# isoDebug-Connectors.net
KiCad netlist of a schematic drawn in Altium Designer
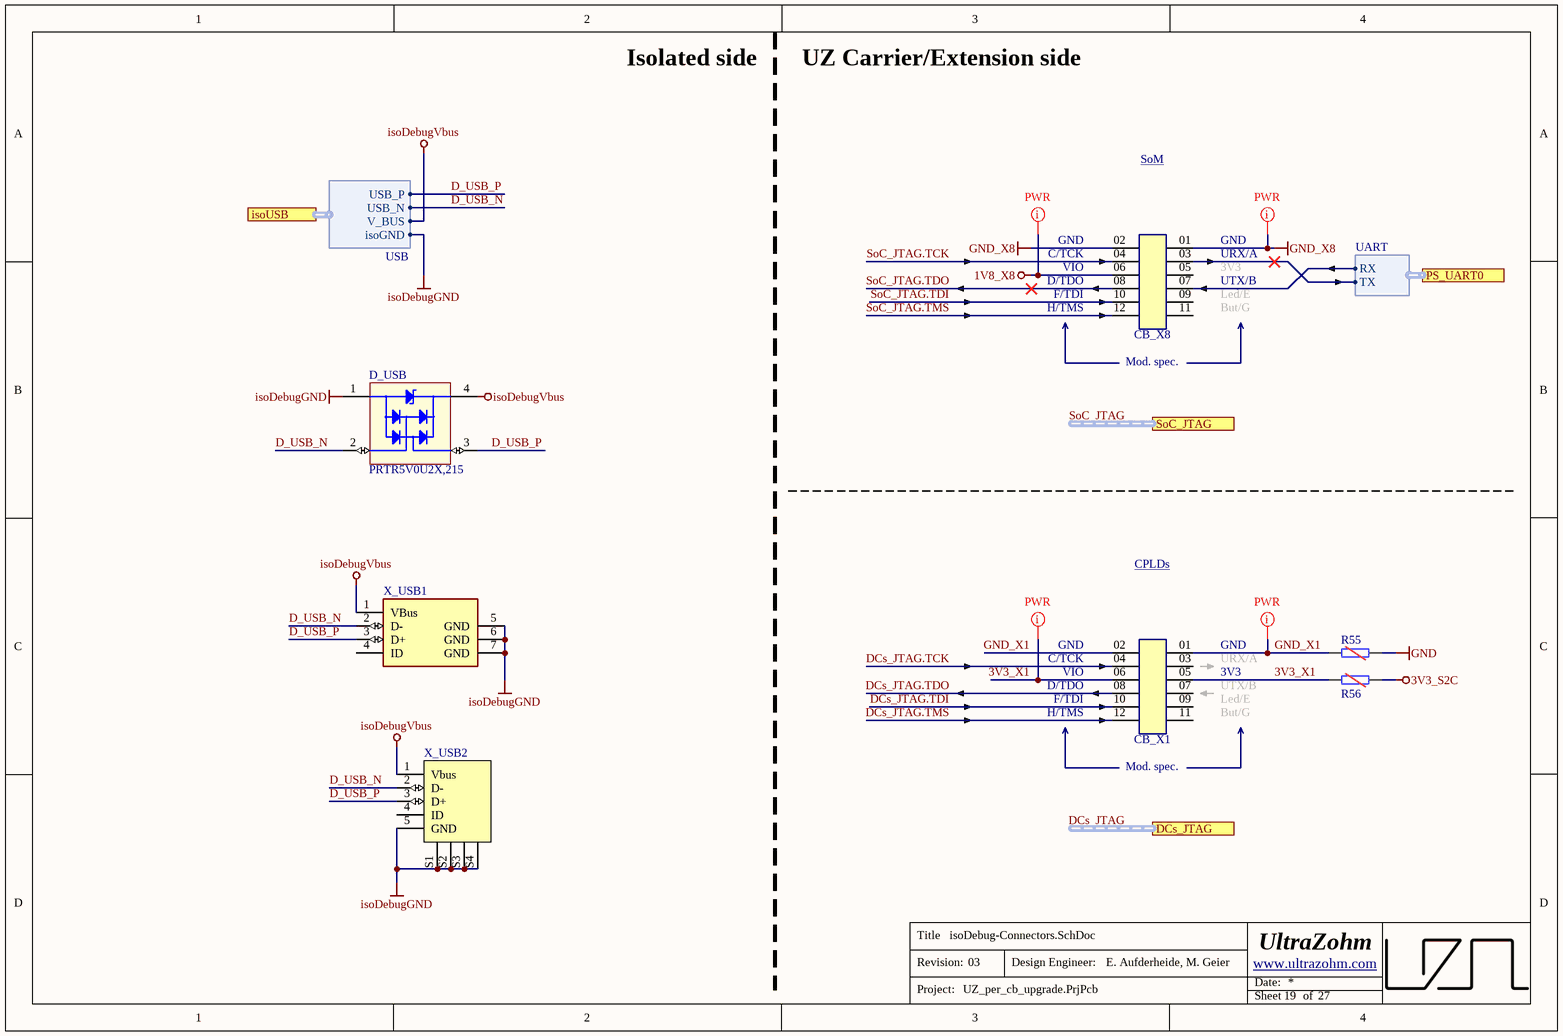
[diagram p0: isoDebug-Connectors.SchDoc]

(export (version "E")
  (design (tool "Eeschema 10.0.6"))
  (components
    (comp (ref "CB_X1")
      (value "PH 0.1\" SMD 2x06")
      (footprint "TSM-106-01-L-DV_Mirrored12+Triangle02")
      (fields
        (field (name "MANUFACTURER PART NUMBER") "UZgen_Conn_PinHead_2x06_SMD_100mil_90deg_mirrored12triangle02")
        (field (name "MANUFACTURER") "UZgen")
        (field (name "CREATED FROM") "UZgenTool")
      )
      (libsource (lib "user") (part "PinHeader_2x06_Mirrored12"))
    )
    (comp (ref "CB_X8")
      (value "PH 0.1\" SMD 2x06")
      (footprint "TSM-106-01-L-DV_Mirrored12+Triangle02")
      (fields
        (field (name "MANUFACTURER PART NUMBER") "UZgen_Conn_PinHead_2x06_SMD_100mil_90deg_mirrored12triangle02")
        (field (name "MANUFACTURER") "UZgen")
        (field (name "CREATED FROM") "UZgenTool")
      )
      (libsource (lib "user") (part "PinHeader_2x06_Mirrored12"))
    )
    (comp (ref "D_USB")
      (value "PRTR5V0U2X,215")
      (footprint "SOT-143B-4")
      (description "ESD Suppressors / TVS Diodes PRTR5V0U2X/SOT143/SOT4")
      (fields
        (field (name "MANUFACTURER") "Nexperia")
        (field (name "LCSC PART NUMBER") "C12333")
        (field (name "CREATED FROM") "AGeiger")
      )
      (libsource (lib "user") (part "CD143A-SRxx"))
    )
    (comp (ref "R55")
      (value "DNP")
      (footprint "R_1206_TE-DNP")
      (description "Generic resistor (DNP)")
      (fields
        (field (name "MANUFACTURER PART NUMBER") "UZgen_R_1206_DNP")
        (field (name "MANUFACTURER") "UZgen")
        (field (name "CREATED FROM") "UZgenTool")
      )
      (libsource (lib "user") (part "RES-DNP"))
    )
    (comp (ref "R56")
      (value "DNP")
      (footprint "R_1206_TE-DNP")
      (description "Generic resistor (DNP)")
      (fields
        (field (name "MANUFACTURER PART NUMBER") "UZgen_R_1206_DNP")
        (field (name "MANUFACTURER") "UZgen")
        (field (name "CREATED FROM") "UZgenTool")
      )
      (libsource (lib "user") (part "RES-DNP"))
    )
    (comp (ref "X_USB1")
      (value "Mini USB 90")
      (footprint "920-462A2021Y10102_CUSTOMANLRING0.2mm")
      (description "USB 2.0 1 5P Female Mini-B Plugin USB Connectors ROHS")
      (fields
        (field (name "MANUFACTURER PART NUMBER") "920-462A2021Y10102")
        (field (name "MANUFACTURER") "Jing Extension of the Electronic Co.")
        (field (name "CREATED FROM") "FRosner")
      )
      (libsource (lib "user") (part "Mini_USB_90"))
    )
    (comp (ref "X_USB2")
      (value "Mini USB")
      (footprint "MINI_USB_5S_B _TYPE")
      (description "1A 1 Surface Mount 5P Female -30℃~+80℃ SMD USB Connectors ROHS")
      (fields
        (field (name "MANUFACTURER PART NUMBER") "MINI 5PTP")
        (field (name "MANUFACTURER") "SHOU HAN")
        (field (name "CREATED FROM") "AGeiger")
      )
      (libsource (lib "user") (part "Mini_USB"))
    )
  )
  (nets
    (net (code "5") (name "/3V3_X1") (class "Default")
      (node (ref "CB_X1") (pin "05") (pinfunction "05_05") (pintype "passive"))
      (node (ref "CB_X1") (pin "06") (pinfunction "06_06") (pintype "passive"))
      (node (ref "R56") (pin "1") (pinfunction "1_1") (pintype "passive"))
    )
    (net (code "6") (name "/DCs_JTAG.TCK") (class "Default")
      (node (ref "CB_X1") (pin "04") (pinfunction "04_04") (pintype "passive"))
    )
    (net (code "7") (name "/DCs_JTAG.TDI") (class "Default")
      (node (ref "CB_X1") (pin "10") (pinfunction "10_10") (pintype "passive"))
    )
    (net (code "8") (name "/DCs_JTAG.TDO") (class "Default")
      (node (ref "CB_X1") (pin "08") (pinfunction "08_08") (pintype "passive"))
    )
    (net (code "9") (name "/DCs_JTAG.TMS") (class "Default")
      (node (ref "CB_X1") (pin "12") (pinfunction "12_12") (pintype "passive"))
    )
    (net (code "10") (name "/D_USB_N") (class "Default")
      (node (ref "D_USB") (pin "2") (pinfunction "I/O_2") (pintype "bidirectional"))
      (node (ref "X_USB1") (pin "2") (pinfunction "D-_2") (pintype "bidirectional"))
      (node (ref "X_USB2") (pin "2") (pinfunction "D-_2") (pintype "bidirectional"))
    )
    (net (code "11") (name "/D_USB_P") (class "Default")
      (node (ref "D_USB") (pin "3") (pinfunction "I/O_3") (pintype "bidirectional"))
      (node (ref "X_USB1") (pin "3") (pinfunction "D+_3") (pintype "bidirectional"))
      (node (ref "X_USB2") (pin "3") (pinfunction "D+_3") (pintype "bidirectional"))
    )
    (net (code "12") (name "/GND_X1") (class "Default")
      (node (ref "CB_X1") (pin "01") (pinfunction "01_01") (pintype "passive"))
      (node (ref "CB_X1") (pin "02") (pinfunction "02_02") (pintype "passive"))
      (node (ref "R55") (pin "1") (pinfunction "1_1") (pintype "passive"))
    )
    (net (code "13") (name "/RX") (class "Default")
      (node (ref "CB_X8") (pin "07") (pinfunction "07_07") (pintype "passive"))
    )
    (net (code "14") (name "/SoC_JTAG.TCK") (class "Default")
      (node (ref "CB_X8") (pin "04") (pinfunction "04_04") (pintype "passive"))
    )
    (net (code "15") (name "/SoC_JTAG.TDI") (class "Default")
      (node (ref "CB_X8") (pin "10") (pinfunction "10_10") (pintype "passive"))
    )
    (net (code "16") (name "/SoC_JTAG.TDO") (class "Default")
      (node (ref "CB_X8") (pin "08") (pinfunction "08_08") (pintype "passive"))
    )
    (net (code "17") (name "/SoC_JTAG.TMS") (class "Default")
      (node (ref "CB_X8") (pin "12") (pinfunction "12_12") (pintype "passive"))
    )
    (net (code "18") (name "/TX") (class "Default")
      (node (ref "CB_X8") (pin "03") (pinfunction "03_03") (pintype "passive"))
    )
    (net (code "23") (name "1V8_X8") (class "Default")
      (node (ref "CB_X8") (pin "06") (pinfunction "06_06") (pintype "passive"))
    )
    (net (code "24") (name "3V3_S2C") (class "Default")
      (node (ref "R56") (pin "2") (pinfunction "2_2") (pintype "passive"))
    )
    (net (code "25") (name "GND") (class "Default")
      (node (ref "R55") (pin "2") (pinfunction "2_2") (pintype "passive"))
    )
    (net (code "26") (name "GND_X8") (class "Default")
      (node (ref "CB_X8") (pin "01") (pinfunction "01_01") (pintype "passive"))
      (node (ref "CB_X8") (pin "02") (pinfunction "02_02") (pintype "passive"))
    )
    (net (code "27") (name "isoDebugGND") (class "Default")
      (node (ref "D_USB") (pin "1") (pinfunction "GND_1") (pintype "passive"))
      (node (ref "X_USB1") (pin "5") (pinfunction "GND_5") (pintype "passive"))
      (node (ref "X_USB1") (pin "6") (pinfunction "GND_6") (pintype "passive"))
      (node (ref "X_USB1") (pin "7") (pinfunction "GND_7") (pintype "passive"))
      (node (ref "X_USB2") (pin "5") (pinfunction "GND_5") (pintype "power_in"))
      (node (ref "X_USB2") (pin "S1") (pinfunction "S1_S1") (pintype "passive"))
      (node (ref "X_USB2") (pin "S2") (pinfunction "S2_S2") (pintype "passive"))
      (node (ref "X_USB2") (pin "S3") (pinfunction "S3_S3") (pintype "passive"))
      (node (ref "X_USB2") (pin "S4") (pinfunction "S4_S4") (pintype "passive"))
    )
    (net (code "28") (name "isoDebugVbus") (class "Default")
      (node (ref "D_USB") (pin "4") (pinfunction "REF_4") (pintype "passive"))
      (node (ref "X_USB1") (pin "1") (pinfunction "VBus_1") (pintype "passive"))
      (node (ref "X_USB2") (pin "1") (pinfunction "Vbus_1") (pintype "power_in"))
    )
    (net (code "29") (name "unconnected-(CB_X1-Pad03)") (class "Default")
      (node (ref "CB_X1") (pin "03") (pinfunction "03_03") (pintype "passive"))
    )
    (net (code "30") (name "unconnected-(CB_X1-Pad07)") (class "Default")
      (node (ref "CB_X1") (pin "07") (pinfunction "07_07") (pintype "passive"))
    )
    (net (code "31") (name "unconnected-(CB_X1-Pad09)") (class "Default")
      (node (ref "CB_X1") (pin "09") (pinfunction "09_09") (pintype "passive"))
    )
    (net (code "32") (name "unconnected-(CB_X1-Pad11)") (class "Default")
      (node (ref "CB_X1") (pin "11") (pinfunction "11_11") (pintype "passive"))
    )
    (net (code "33") (name "unconnected-(CB_X8-Pad05)") (class "Default")
      (node (ref "CB_X8") (pin "05") (pinfunction "05_05") (pintype "passive"))
    )
    (net (code "34") (name "unconnected-(CB_X8-Pad09)") (class "Default")
      (node (ref "CB_X8") (pin "09") (pinfunction "09_09") (pintype "passive"))
    )
    (net (code "35") (name "unconnected-(CB_X8-Pad11)") (class "Default")
      (node (ref "CB_X8") (pin "11") (pinfunction "11_11") (pintype "passive"))
    )
    (net (code "36") (name "unconnected-(X_USB1-ID-Pad4)") (class "Default")
      (node (ref "X_USB1") (pin "4") (pinfunction "ID_4") (pintype "passive"))
    )
    (net (code "37") (name "unconnected-(X_USB2-ID-Pad4)") (class "Default")
      (node (ref "X_USB2") (pin "4") (pinfunction "ID_4") (pintype "passive"))
    )
  )
)
